# Rauch.net
KiCad netlist of a schematic drawn in Altium Designer
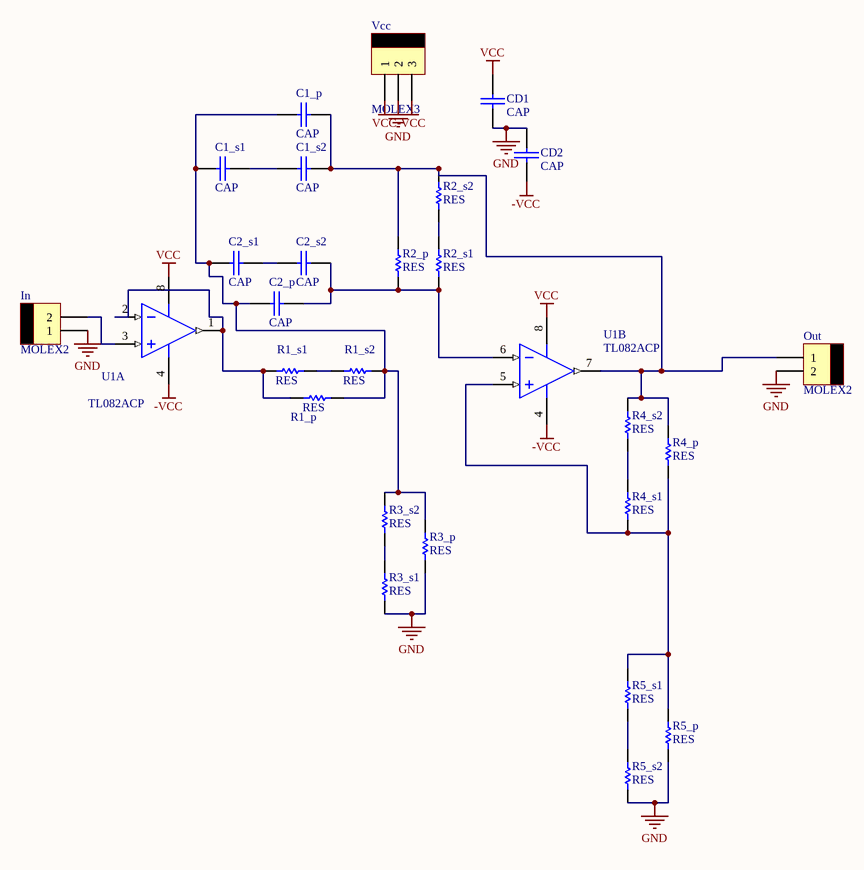
[diagram p0: Rauch.SchDoc]

(export (version "E")
  (design (tool "Eeschema 10.0.6"))
  (components
    (comp (ref "C1_p") (value "CAP") (footprint "0805") (libsource (lib "LIB PIO IX") (part "CAP")))
    (comp (ref "C1_s1") (value "CAP") (footprint "0805") (libsource (lib "LIB PIO IX") (part "CAP")))
    (comp (ref "C1_s2") (value "CAP") (footprint "0805") (libsource (lib "LIB PIO IX") (part "CAP")))
    (comp (ref "C2_p") (value "CAP") (footprint "0805") (libsource (lib "LIB PIO IX") (part "CAP")))
    (comp (ref "C2_s1") (value "CAP") (footprint "0805") (libsource (lib "LIB PIO IX") (part "CAP")))
    (comp (ref "C2_s2") (value "CAP") (footprint "0805") (libsource (lib "LIB PIO IX") (part "CAP")))
    (comp (ref "CD1") (value "CAP") (footprint "0805") (libsource (lib "LIB PIO IX") (part "CAP")))
    (comp (ref "CD2") (value "CAP") (footprint "0805") (libsource (lib "LIB PIO IX") (part "CAP")))
    (comp (ref "In") (value "MOLEX2") (footprint "MOLEX2") (libsource (lib "") (part "MOLEX2_1")))
    (comp (ref "Out") (value "MOLEX2") (footprint "MOLEX2") (libsource (lib "LIB PIO IX") (part "MOLEX2")))
    (comp (ref "R1_p") (value "RES") (footprint "0805") (libsource (lib "LIB PIO IX") (part "RES")))
    (comp (ref "R1_s1") (value "RES") (footprint "0805") (libsource (lib "LIB PIO IX") (part "RES")))
    (comp (ref "R1_s2") (value "RES") (footprint "0805") (libsource (lib "LIB PIO IX") (part "RES")))
    (comp (ref "R2_p") (value "RES") (footprint "0805") (libsource (lib "LIB PIO IX") (part "RES")))
    (comp (ref "R2_s1") (value "RES") (footprint "0805") (libsource (lib "LIB PIO IX") (part "RES")))
    (comp (ref "R2_s2") (value "RES") (footprint "0805") (libsource (lib "LIB PIO IX") (part "RES")))
    (comp (ref "R3_p") (value "RES") (footprint "0805") (libsource (lib "LIB PIO IX") (part "RES")))
    (comp (ref "R3_s1") (value "RES") (footprint "0805") (libsource (lib "LIB PIO IX") (part "RES")))
    (comp (ref "R3_s2") (value "RES") (footprint "0805") (libsource (lib "LIB PIO IX") (part "RES")))
    (comp (ref "R4_p") (value "RES") (footprint "0805") (libsource (lib "LIB PIO IX") (part "RES")))
    (comp (ref "R4_s1") (value "RES") (footprint "0805") (libsource (lib "LIB PIO IX") (part "RES")))
    (comp (ref "R4_s2") (value "RES") (footprint "0805") (libsource (lib "LIB PIO IX") (part "RES")))
    (comp (ref "R5_p") (value "RES") (footprint "0805") (libsource (lib "LIB PIO IX") (part "RES")))
    (comp (ref "R5_s1") (value "RES") (footprint "0805") (libsource (lib "LIB PIO IX") (part "RES")))
    (comp (ref "R5_s2") (value "RES") (footprint "0805") (libsource (lib "LIB PIO IX") (part "RES")))
    (comp (ref "U1")
      (value "TL082ACP")
      (footprint "TI-P8")
      (description "JFET-Input Operational Amplifier, 7 to 36 V, 0 to 70 degC, 8-pin DIP (P8), Pb-Free (RoHS)")
      (fields (field (name "MANUFACTURER") "Texas Instruments"))
      (libsource (lib "TI Amplifiers and Linear Operational Amplifier General Purpose") (part "TL082ACP"))
    )
    (comp (ref "Vcc") (value "MOLEX3") (footprint "MOLEX3") (libsource (lib "LIB PIO IX") (part "MOLEX3")))
  )
  (nets
    (net (code "1") (name "-VCC") (class "Default")
      (node (ref "CD2") (pin "2") (pinfunction "2_2") (pintype "passive"))
      (node (ref "U1") (pin "4") (pinfunction "VCC-_4") (pintype "power_in"))
      (node (ref "Vcc") (pin "3") (pinfunction "3_3") (pintype "passive"))
    )
    (net (code "2") (name "GND") (class "Default")
      (node (ref "CD1") (pin "2") (pinfunction "2_2") (pintype "passive"))
      (node (ref "CD2") (pin "1") (pinfunction "1_1") (pintype "passive"))
      (node (ref "In") (pin "1") (pinfunction "1_1") (pintype "passive"))
      (node (ref "Out") (pin "2") (pinfunction "2_2") (pintype "passive"))
      (node (ref "R3_p") (pin "1") (pinfunction "1_1") (pintype "passive"))
      (node (ref "R3_s1") (pin "1") (pinfunction "1_1") (pintype "passive"))
      (node (ref "R5_p") (pin "1") (pinfunction "1_1") (pintype "passive"))
      (node (ref "R5_s2") (pin "1") (pinfunction "1_1") (pintype "passive"))
      (node (ref "Vcc") (pin "2") (pinfunction "2_2") (pintype "passive"))
    )
    (net (code "3") (name "Net-(C1_p-Pad1)") (class "Default")
      (node (ref "C1_p") (pin "1") (pinfunction "1_1") (pintype "passive"))
      (node (ref "C1_s1") (pin "1") (pinfunction "1_1") (pintype "passive"))
      (node (ref "C2_p") (pin "1") (pinfunction "1_1") (pintype "passive"))
      (node (ref "C2_s1") (pin "1") (pinfunction "1_1") (pintype "passive"))
      (node (ref "R1_p") (pin "2") (pinfunction "2_2") (pintype "passive"))
      (node (ref "R1_s2") (pin "2") (pinfunction "2_2") (pintype "passive"))
      (node (ref "R3_p") (pin "2") (pinfunction "2_2") (pintype "passive"))
      (node (ref "R3_s2") (pin "2") (pinfunction "2_2") (pintype "passive"))
    )
    (net (code "4") (name "Net-(C1_s1-Pad2)") (class "Default")
      (node (ref "C1_s1") (pin "2") (pinfunction "2_2") (pintype "passive"))
      (node (ref "C1_s2") (pin "1") (pinfunction "1_1") (pintype "passive"))
    )
    (net (code "5") (name "Net-(C2_s1-Pad2)") (class "Default")
      (node (ref "C2_s1") (pin "2") (pinfunction "2_2") (pintype "passive"))
      (node (ref "C2_s2") (pin "1") (pinfunction "1_1") (pintype "passive"))
    )
    (net (code "6") (name "Net-(R1_s1-Pad2)") (class "Default")
      (node (ref "R1_s1") (pin "2") (pinfunction "2_2") (pintype "passive"))
      (node (ref "R1_s2") (pin "1") (pinfunction "1_1") (pintype "passive"))
    )
    (net (code "7") (name "Net-(R2_s1-Pad2)") (class "Default")
      (node (ref "R2_s1") (pin "2") (pinfunction "2_2") (pintype "passive"))
      (node (ref "R2_s2") (pin "1") (pinfunction "1_1") (pintype "passive"))
    )
    (net (code "8") (name "Net-(R3_s1-Pad2)") (class "Default")
      (node (ref "R3_s1") (pin "2") (pinfunction "2_2") (pintype "passive"))
      (node (ref "R3_s2") (pin "1") (pinfunction "1_1") (pintype "passive"))
    )
    (net (code "9") (name "Net-(R4_s1-Pad2)") (class "Default")
      (node (ref "R4_s1") (pin "2") (pinfunction "2_2") (pintype "passive"))
      (node (ref "R4_s2") (pin "1") (pinfunction "1_1") (pintype "passive"))
    )
    (net (code "10") (name "Net-(R5_s1-Pad1)") (class "Default")
      (node (ref "R5_s1") (pin "1") (pinfunction "1_1") (pintype "passive"))
      (node (ref "R5_s2") (pin "2") (pinfunction "2_2") (pintype "passive"))
    )
    (net (code "11") (name "Net-(U1A-IN1+)") (class "Default")
      (node (ref "In") (pin "2") (pinfunction "2_2") (pintype "passive"))
      (node (ref "U1") (pin "3") (pinfunction "IN1+_3") (pintype "input"))
    )
    (net (code "12") (name "Net-(U1A-IN1-)") (class "Default")
      (node (ref "R1_p") (pin "1") (pinfunction "1_1") (pintype "passive"))
      (node (ref "R1_s1") (pin "1") (pinfunction "1_1") (pintype "passive"))
      (node (ref "U1") (pin "1") (pinfunction "OUT1_1") (pintype "output"))
      (node (ref "U1") (pin "2") (pinfunction "IN1-_2") (pintype "input"))
    )
    (net (code "13") (name "Net-(U1B-IN2+)") (class "Default")
      (node (ref "R4_p") (pin "1") (pinfunction "1_1") (pintype "passive"))
      (node (ref "R4_s1") (pin "1") (pinfunction "1_1") (pintype "passive"))
      (node (ref "R5_p") (pin "2") (pinfunction "2_2") (pintype "passive"))
      (node (ref "R5_s1") (pin "2") (pinfunction "2_2") (pintype "passive"))
      (node (ref "U1") (pin "5") (pinfunction "IN2+_5") (pintype "input"))
    )
    (net (code "14") (name "Net-(U1B-IN2-)") (class "Default")
      (node (ref "C2_p") (pin "2") (pinfunction "2_2") (pintype "passive"))
      (node (ref "C2_s2") (pin "2") (pinfunction "2_2") (pintype "passive"))
      (node (ref "R2_p") (pin "1") (pinfunction "1_1") (pintype "passive"))
      (node (ref "R2_s1") (pin "1") (pinfunction "1_1") (pintype "passive"))
      (node (ref "U1") (pin "6") (pinfunction "IN2-_6") (pintype "input"))
    )
    (net (code "15") (name "Net-(U1B-OUT2)") (class "Default")
      (node (ref "C1_p") (pin "2") (pinfunction "2_2") (pintype "passive"))
      (node (ref "C1_s2") (pin "2") (pinfunction "2_2") (pintype "passive"))
      (node (ref "Out") (pin "1") (pinfunction "1_1") (pintype "passive"))
      (node (ref "R2_p") (pin "2") (pinfunction "2_2") (pintype "passive"))
      (node (ref "R2_s2") (pin "2") (pinfunction "2_2") (pintype "passive"))
      (node (ref "R4_p") (pin "2") (pinfunction "2_2") (pintype "passive"))
      (node (ref "R4_s2") (pin "2") (pinfunction "2_2") (pintype "passive"))
      (node (ref "U1") (pin "7") (pinfunction "OUT2_7") (pintype "output"))
    )
    (net (code "16") (name "VCC") (class "Default")
      (node (ref "CD1") (pin "1") (pinfunction "1_1") (pintype "passive"))
      (node (ref "U1") (pin "8") (pinfunction "VCC+_8") (pintype "power_in"))
      (node (ref "Vcc") (pin "1") (pinfunction "1_1") (pintype "passive"))
    )
  )
)
